# ethernetGateway.net
KiCad netlist of a schematic drawn in EAGLE
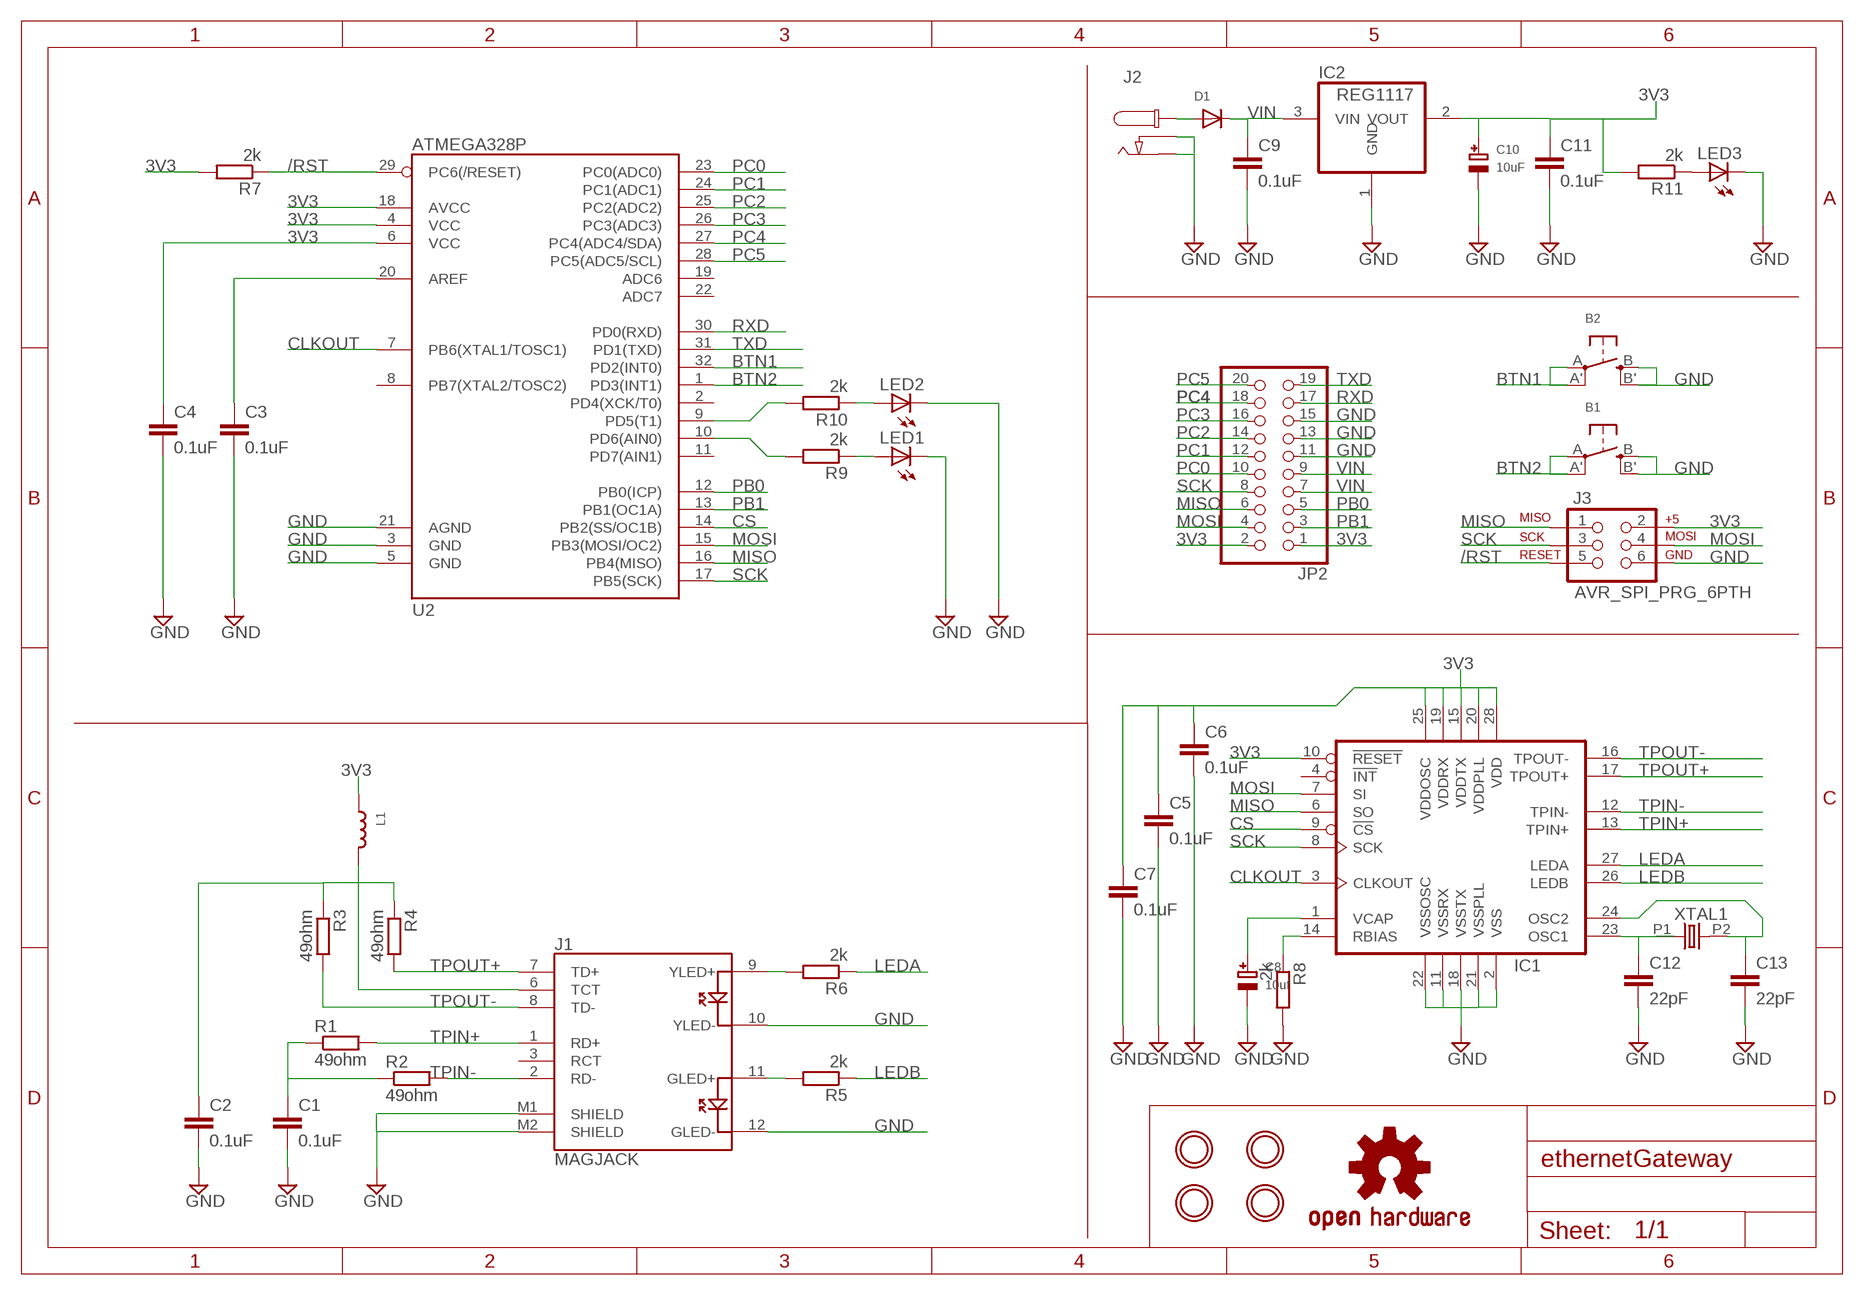
[diagram p0: schematic, sheet 1]

(export (version "E")
  (design (tool "Eeschema 10.0.6"))
  (components
    (comp (ref "B1")
      (value "SWITCH_TACT_SMT4.6X2.8")
      (footprint "eagle-import:BTN_KMR2_4.6X2.8")
      (libsource (lib "eagle-import") (part "SWITCH_TACT_SMT4.6X2.8"))
    )
    (comp (ref "B2")
      (value "SWITCH_TACT_SMT4.6X2.8")
      (footprint "eagle-import:BTN_KMR2_4.6X2.8")
      (libsource (lib "eagle-import") (part "SWITCH_TACT_SMT4.6X2.8"))
    )
    (comp (ref "C1")
      (value "0.1uF")
      (footprint "eagle-import:C0805")
      (libsource (lib "eagle-import") (part "C-EUC0805"))
    )
    (comp (ref "C2")
      (value "0.1uF")
      (footprint "eagle-import:C0805")
      (libsource (lib "eagle-import") (part "C-EUC0805"))
    )
    (comp (ref "C3")
      (value "0.1uF")
      (footprint "eagle-import:C0805")
      (libsource (lib "eagle-import") (part "C-EUC0805"))
    )
    (comp (ref "C4")
      (value "0.1uF")
      (footprint "eagle-import:C0805")
      (libsource (lib "eagle-import") (part "C-EUC0805"))
    )
    (comp (ref "C5")
      (value "0.1uF")
      (footprint "eagle-import:C0805")
      (libsource (lib "eagle-import") (part "C-EUC0805"))
    )
    (comp (ref "C6")
      (value "0.1uF")
      (footprint "eagle-import:C0805")
      (libsource (lib "eagle-import") (part "C-EUC0805"))
    )
    (comp (ref "C7")
      (value "0.1uF")
      (footprint "eagle-import:C0805")
      (libsource (lib "eagle-import") (part "C-EUC0805"))
    )
    (comp (ref "C8")
      (value "10uf")
      (footprint "eagle-import:EIA3528-21_B-W")
      (libsource (lib "eagle-import") (part "CAP_TANTALUMB/3528_WAVE"))
    )
    (comp (ref "C9")
      (value "0.1uF")
      (footprint "eagle-import:C0805")
      (libsource (lib "eagle-import") (part "C-EUC0805"))
    )
    (comp (ref "C10")
      (value "10uF")
      (footprint "eagle-import:EIA3528-21_B-W")
      (libsource (lib "eagle-import") (part "CAP_TANTALUMB/3528_WAVE"))
    )
    (comp (ref "C11")
      (value "0.1uF")
      (footprint "eagle-import:C0805")
      (libsource (lib "eagle-import") (part "C-EUC0805"))
    )
    (comp (ref "C12")
      (value "22pF")
      (footprint "eagle-import:C0805")
      (libsource (lib "eagle-import") (part "C-EUC0805"))
    )
    (comp (ref "C13")
      (value "22pF")
      (footprint "eagle-import:C0805")
      (libsource (lib "eagle-import") (part "C-EUC0805"))
    )
    (comp (ref "D1")
      (value "DIODEDO-1N4148")
      (footprint "eagle-import:DO-1N4148")
      (libsource (lib "eagle-import") (part "DIODEDO-1N4148"))
    )
    (comp (ref "IC1")
      (value "IC_ENC28J60-SOIC-28")
      (footprint "eagle-import:SOIC-28W")
      (libsource (lib "eagle-import") (part "IC_ENC28J60-SOIC-28"))
    )
    (comp (ref "IC2")
      (value "REG1117")
      (footprint "eagle-import:SOT223")
      (libsource (lib "eagle-import") (part "REG1117"))
    )
    (comp (ref "J1")
      (value "MAGJACK")
      (footprint "eagle-import:MAGJACK")
      (libsource (lib "eagle-import") (part "MAGJACK"))
    )
    (comp (ref "J2")
      (value "CON_DC_M-DC_PTH")
      (footprint "eagle-import:DC_BARREL_JACK_PTH_2MM")
      (libsource (lib "eagle-import") (part "CON_DC_M-DC_PTH"))
    )
    (comp (ref "J3")
      (value "AVR_SPI_PRG_6PTH")
      (footprint "eagle-import:2X3")
      (libsource (lib "eagle-import") (part "AVR_SPI_PRG_6PTH"))
    )
    (comp (ref "JP2")
      (value "PINHD-2X10")
      (footprint "eagle-import:2X10")
      (libsource (lib "eagle-import") (part "PINHD-2X10"))
    )
    (comp (ref "L1")
      (value "INDUCTOR0805")
      (footprint "eagle-import:0805")
      (libsource (lib "eagle-import") (part "INDUCTOR0805"))
    )
    (comp (ref "LED1")
      (value "LED-0805")
      (footprint "eagle-import:LED-805")
      (libsource (lib "eagle-import") (part "LED-0805"))
    )
    (comp (ref "LED2")
      (value "LED-0805")
      (footprint "eagle-import:LED-805")
      (libsource (lib "eagle-import") (part "LED-0805"))
    )
    (comp (ref "LED3")
      (value "LED-0805")
      (footprint "eagle-import:LED-805")
      (libsource (lib "eagle-import") (part "LED-0805"))
    )
    (comp (ref "LOGO1")
      (value "OSHW-LOGOL")
      (footprint "eagle-import:OSHW-LOGO-L")
      (libsource (lib "eagle-import") (part "OSHW-LOGOL"))
    )
    (comp (ref "R1")
      (value "49ohm")
      (footprint "eagle-import:R0805")
      (libsource (lib "eagle-import") (part "R-EU_R0805"))
    )
    (comp (ref "R2")
      (value "49ohm")
      (footprint "eagle-import:R0805")
      (libsource (lib "eagle-import") (part "R-EU_R0805"))
    )
    (comp (ref "R3")
      (value "49ohm")
      (footprint "eagle-import:R0805")
      (libsource (lib "eagle-import") (part "R-EU_R0805"))
    )
    (comp (ref "R4")
      (value "49ohm")
      (footprint "eagle-import:R0805")
      (libsource (lib "eagle-import") (part "R-EU_R0805"))
    )
    (comp (ref "R5")
      (value "2k")
      (footprint "eagle-import:R0805")
      (libsource (lib "eagle-import") (part "R-EU_R0805"))
    )
    (comp (ref "R6")
      (value "2k")
      (footprint "eagle-import:R0805")
      (libsource (lib "eagle-import") (part "R-EU_R0805"))
    )
    (comp (ref "R7")
      (value "2k")
      (footprint "eagle-import:R0805")
      (libsource (lib "eagle-import") (part "R-EU_R0805"))
    )
    (comp (ref "R8")
      (value "2k")
      (footprint "eagle-import:R0805")
      (libsource (lib "eagle-import") (part "R-EU_R0805"))
    )
    (comp (ref "R9")
      (value "2k")
      (footprint "eagle-import:R0805")
      (libsource (lib "eagle-import") (part "R-EU_R0805"))
    )
    (comp (ref "R10")
      (value "2k")
      (footprint "eagle-import:R0805")
      (libsource (lib "eagle-import") (part "R-EU_R0805"))
    )
    (comp (ref "R11")
      (value "2k")
      (footprint "eagle-import:R0805")
      (libsource (lib "eagle-import") (part "R-EU_R0805"))
    )
    (comp (ref "U$1")
      (value "MOUNTINGHOLE2.0")
      (footprint "eagle-import:MOUNTINGHOLE_2.0_PLATED")
      (libsource (lib "eagle-import") (part "MOUNTINGHOLE2.0"))
    )
    (comp (ref "U$2")
      (value "MOUNTINGHOLE2.0")
      (footprint "eagle-import:MOUNTINGHOLE_2.0_PLATED")
      (libsource (lib "eagle-import") (part "MOUNTINGHOLE2.0"))
    )
    (comp (ref "U$3")
      (value "MOUNTINGHOLE2.0")
      (footprint "eagle-import:MOUNTINGHOLE_2.0_PLATED")
      (libsource (lib "eagle-import") (part "MOUNTINGHOLE2.0"))
    )
    (comp (ref "U$4")
      (value "MOUNTINGHOLE2.0")
      (footprint "eagle-import:MOUNTINGHOLE_2.0_PLATED")
      (libsource (lib "eagle-import") (part "MOUNTINGHOLE2.0"))
    )
    (comp (ref "U2")
      (value "ATMEGA328P")
      (footprint "eagle-import:TQFP32-08")
      (libsource (lib "eagle-import") (part "ATMEGA328_SMT"))
    )
    (comp (ref "XTAL1")
      (value "OSC-XTAL-HC-49U-PTH")
      (footprint "eagle-import:HC-49U-PTH")
      (libsource (lib "eagle-import") (part "OSC-XTAL-HC-49U-PTH"))
    )
  )
  (nets
    (net (code "1") (name "/3V3") (class "Default")
      (node (ref "C10") (pin "+") (pinfunction "+_+") (pintype "passive"))
      (node (ref "C11") (pin "1") (pinfunction "1_1") (pintype "passive"))
      (node (ref "C4") (pin "1") (pinfunction "1_1") (pintype "passive"))
      (node (ref "C5") (pin "1") (pinfunction "1_1") (pintype "passive"))
      (node (ref "C6") (pin "1") (pinfunction "1_1") (pintype "passive"))
      (node (ref "C7") (pin "1") (pinfunction "1_1") (pintype "passive"))
      (node (ref "IC1") (pin "10") (pinfunction "~{RESET}_10") (pintype "input"))
      (node (ref "IC1") (pin "15") (pinfunction "VDDTX_15") (pintype "power_in"))
      (node (ref "IC1") (pin "19") (pinfunction "VDDRX_19") (pintype "power_in"))
      (node (ref "IC1") (pin "20") (pinfunction "VDDPLL_20") (pintype "power_in"))
      (node (ref "IC1") (pin "25") (pinfunction "VDDOSC_25") (pintype "power_in"))
      (node (ref "IC1") (pin "28") (pinfunction "VDD_28") (pintype "power_in"))
      (node (ref "IC2") (pin "2") (pinfunction "VOUT_2") (pintype "output"))
      (node (ref "J3") (pin "2") (pinfunction "2_2") (pintype "passive"))
      (node (ref "JP2") (pin "1") (pinfunction "1_1") (pintype "passive"))
      (node (ref "JP2") (pin "2") (pinfunction "2_2") (pintype "passive"))
      (node (ref "L1") (pin "1") (pinfunction "1_1") (pintype "passive"))
      (node (ref "R11") (pin "2") (pinfunction "2_2") (pintype "passive"))
      (node (ref "R7") (pin "2") (pinfunction "2_2") (pintype "passive"))
      (node (ref "U2") (pin "18") (pinfunction "AVCC_18") (pintype "bidirectional"))
      (node (ref "U2") (pin "4") (pinfunction "VCC_4") (pintype "bidirectional"))
      (node (ref "U2") (pin "6") (pinfunction "VCC_6") (pintype "bidirectional"))
    )
    (net (code "2") (name "/BTN1") (class "Default")
      (node (ref "B2") (pin "A") (pinfunction "P_A") (pintype "passive"))
      (node (ref "B2") (pin "A'") (pinfunction "P1_A'") (pintype "passive"))
      (node (ref "U2") (pin "32") (pinfunction "PD2(INT0)_32") (pintype "bidirectional"))
    )
    (net (code "3") (name "/BTN2") (class "Default")
      (node (ref "B1") (pin "A") (pinfunction "P_A") (pintype "passive"))
      (node (ref "B1") (pin "A'") (pinfunction "P1_A'") (pintype "passive"))
      (node (ref "U2") (pin "1") (pinfunction "PD3(INT1)_1") (pintype "bidirectional"))
    )
    (net (code "4") (name "/CLKOUT") (class "Default")
      (node (ref "IC1") (pin "3") (pinfunction "CLKOUT_3") (pintype "output"))
      (node (ref "U2") (pin "7") (pinfunction "PB6(XTAL1/TOSC1)_7") (pintype "bidirectional"))
    )
    (net (code "5") (name "/CS") (class "Default")
      (node (ref "IC1") (pin "9") (pinfunction "~{CS}_9") (pintype "input"))
      (node (ref "U2") (pin "14") (pinfunction "PB2(SS/OC1B)_14") (pintype "bidirectional"))
    )
    (net (code "6") (name "/LEDA") (class "Default")
      (node (ref "IC1") (pin "27") (pinfunction "LEDA_27") (pintype "output"))
      (node (ref "R6") (pin "1") (pinfunction "1_1") (pintype "passive"))
    )
    (net (code "7") (name "/LEDB") (class "Default")
      (node (ref "IC1") (pin "26") (pinfunction "LEDB_26") (pintype "output"))
      (node (ref "R5") (pin "1") (pinfunction "1_1") (pintype "passive"))
    )
    (net (code "8") (name "/MISO") (class "Default")
      (node (ref "IC1") (pin "6") (pinfunction "SO_6") (pintype "output"))
      (node (ref "J3") (pin "1") (pinfunction "1_1") (pintype "passive"))
      (node (ref "JP2") (pin "6") (pinfunction "6_6") (pintype "passive"))
      (node (ref "U2") (pin "16") (pinfunction "PB4(MISO)_16") (pintype "bidirectional"))
    )
    (net (code "9") (name "/MOSI") (class "Default")
      (node (ref "IC1") (pin "7") (pinfunction "SI_7") (pintype "input"))
      (node (ref "J3") (pin "4") (pinfunction "4_4") (pintype "passive"))
      (node (ref "JP2") (pin "4") (pinfunction "4_4") (pintype "passive"))
      (node (ref "U2") (pin "15") (pinfunction "PB3(MOSI/OC2)_15") (pintype "bidirectional"))
    )
    (net (code "10") (name "/PB0") (class "Default")
      (node (ref "JP2") (pin "5") (pinfunction "5_5") (pintype "passive"))
      (node (ref "U2") (pin "12") (pinfunction "PB0(ICP)_12") (pintype "bidirectional"))
    )
    (net (code "11") (name "/PB1") (class "Default")
      (node (ref "JP2") (pin "3") (pinfunction "3_3") (pintype "passive"))
      (node (ref "U2") (pin "13") (pinfunction "PB1(OC1A)_13") (pintype "bidirectional"))
    )
    (net (code "12") (name "/PC0") (class "Default")
      (node (ref "JP2") (pin "10") (pinfunction "10_10") (pintype "passive"))
      (node (ref "U2") (pin "23") (pinfunction "PC0(ADC0)_23") (pintype "bidirectional"))
    )
    (net (code "13") (name "/PC1") (class "Default")
      (node (ref "JP2") (pin "12") (pinfunction "12_12") (pintype "passive"))
      (node (ref "U2") (pin "24") (pinfunction "PC1(ADC1)_24") (pintype "bidirectional"))
    )
    (net (code "14") (name "/PC2") (class "Default")
      (node (ref "JP2") (pin "14") (pinfunction "14_14") (pintype "passive"))
      (node (ref "U2") (pin "25") (pinfunction "PC2(ADC2)_25") (pintype "bidirectional"))
    )
    (net (code "15") (name "/PC3") (class "Default")
      (node (ref "JP2") (pin "16") (pinfunction "16_16") (pintype "passive"))
      (node (ref "U2") (pin "26") (pinfunction "PC3(ADC3)_26") (pintype "bidirectional"))
    )
    (net (code "16") (name "/PC4") (class "Default")
      (node (ref "JP2") (pin "18") (pinfunction "18_18") (pintype "passive"))
      (node (ref "U2") (pin "27") (pinfunction "PC4(ADC4/SDA)_27") (pintype "bidirectional"))
    )
    (net (code "17") (name "/PC5") (class "Default")
      (node (ref "JP2") (pin "20") (pinfunction "20_20") (pintype "passive"))
      (node (ref "U2") (pin "28") (pinfunction "PC5(ADC5/SCL)_28") (pintype "bidirectional"))
    )
    (net (code "18") (name "/RXD") (class "Default")
      (node (ref "JP2") (pin "17") (pinfunction "17_17") (pintype "passive"))
      (node (ref "U2") (pin "30") (pinfunction "PD0(RXD)_30") (pintype "bidirectional"))
    )
    (net (code "19") (name "/SCK") (class "Default")
      (node (ref "IC1") (pin "8") (pinfunction "SCK_8") (pintype "input"))
      (node (ref "J3") (pin "3") (pinfunction "3_3") (pintype "passive"))
      (node (ref "JP2") (pin "8") (pinfunction "8_8") (pintype "passive"))
      (node (ref "U2") (pin "17") (pinfunction "PB5(SCK)_17") (pintype "bidirectional"))
    )
    (net (code "20") (name "/TPIN+") (class "Default")
      (node (ref "IC1") (pin "13") (pinfunction "TPIN+_13") (pintype "input"))
      (node (ref "J1") (pin "1") (pinfunction "RD+_1") (pintype "bidirectional"))
      (node (ref "R1") (pin "2") (pinfunction "2_2") (pintype "passive"))
    )
    (net (code "21") (name "/TPIN-") (class "Default")
      (node (ref "IC1") (pin "12") (pinfunction "TPIN-_12") (pintype "input"))
      (node (ref "J1") (pin "2") (pinfunction "RD-_2") (pintype "bidirectional"))
      (node (ref "R2") (pin "2") (pinfunction "2_2") (pintype "passive"))
    )
    (net (code "22") (name "/TPOUT+") (class "Default")
      (node (ref "IC1") (pin "17") (pinfunction "TPOUT+_17") (pintype "output"))
      (node (ref "J1") (pin "7") (pinfunction "TD+_7") (pintype "bidirectional"))
      (node (ref "R4") (pin "2") (pinfunction "2_2") (pintype "passive"))
    )
    (net (code "23") (name "/TPOUT-") (class "Default")
      (node (ref "IC1") (pin "16") (pinfunction "TPOUT-_16") (pintype "output"))
      (node (ref "J1") (pin "8") (pinfunction "TD-_8") (pintype "bidirectional"))
      (node (ref "R3") (pin "2") (pinfunction "2_2") (pintype "passive"))
    )
    (net (code "24") (name "/TXD") (class "Default")
      (node (ref "JP2") (pin "19") (pinfunction "19_19") (pintype "passive"))
      (node (ref "U2") (pin "31") (pinfunction "PD1(TXD)_31") (pintype "bidirectional"))
    )
    (net (code "25") (name "/VIN") (class "Default")
      (node (ref "C9") (pin "1") (pinfunction "1_1") (pintype "passive"))
      (node (ref "D1") (pin "C") (pinfunction "C_C") (pintype "passive"))
      (node (ref "IC2") (pin "3") (pinfunction "VIN_3") (pintype "input"))
      (node (ref "JP2") (pin "7") (pinfunction "7_7") (pintype "passive"))
      (node (ref "JP2") (pin "9") (pinfunction "9_9") (pintype "passive"))
    )
    (net (code "26") (name "/{slash}RST") (class "Default")
      (node (ref "J3") (pin "5") (pinfunction "5_5") (pintype "passive"))
      (node (ref "R7") (pin "1") (pinfunction "1_1") (pintype "passive"))
      (node (ref "U2") (pin "29") (pinfunction "PC6(/RESET)_29") (pintype "bidirectional"))
    )
    (net (code "27") (name "GND") (class "Default")
      (node (ref "B1") (pin "B") (pinfunction "S_B") (pintype "passive"))
      (node (ref "B1") (pin "B'") (pinfunction "S1_B'") (pintype "passive"))
      (node (ref "B2") (pin "B") (pinfunction "S_B") (pintype "passive"))
      (node (ref "B2") (pin "B'") (pinfunction "S1_B'") (pintype "passive"))
      (node (ref "C1") (pin "2") (pinfunction "2_2") (pintype "passive"))
      (node (ref "C10") (pin "-") (pinfunction "-_-") (pintype "passive"))
      (node (ref "C11") (pin "2") (pinfunction "2_2") (pintype "passive"))
      (node (ref "C12") (pin "2") (pinfunction "2_2") (pintype "passive"))
      (node (ref "C13") (pin "2") (pinfunction "2_2") (pintype "passive"))
      (node (ref "C2") (pin "2") (pinfunction "2_2") (pintype "passive"))
      (node (ref "C3") (pin "2") (pinfunction "2_2") (pintype "passive"))
      (node (ref "C4") (pin "2") (pinfunction "2_2") (pintype "passive"))
      (node (ref "C5") (pin "2") (pinfunction "2_2") (pintype "passive"))
      (node (ref "C6") (pin "2") (pinfunction "2_2") (pintype "passive"))
      (node (ref "C7") (pin "2") (pinfunction "2_2") (pintype "passive"))
      (node (ref "C8") (pin "-") (pinfunction "-_-") (pintype "passive"))
      (node (ref "C9") (pin "2") (pinfunction "2_2") (pintype "passive"))
      (node (ref "IC1") (pin "11") (pinfunction "VSSRX_11") (pintype "power_in"))
      (node (ref "IC1") (pin "18") (pinfunction "VSSTX_18") (pintype "power_in"))
      (node (ref "IC1") (pin "2") (pinfunction "VSS_2") (pintype "power_in"))
      (node (ref "IC1") (pin "21") (pinfunction "VSSPLL_21") (pintype "power_in"))
      (node (ref "IC1") (pin "22") (pinfunction "VSSOSC_22") (pintype "power_in"))
      (node (ref "IC2") (pin "1") (pinfunction "GND_1") (pintype "power_in"))
      (node (ref "J1") (pin "10") (pinfunction "YLED-_10") (pintype "bidirectional"))
      (node (ref "J1") (pin "12") (pinfunction "GLED-_12") (pintype "bidirectional"))
      (node (ref "J1") (pin "M1") (pinfunction "SHIELD_M1") (pintype "bidirectional"))
      (node (ref "J1") (pin "M2") (pinfunction "SHIELD_M2") (pintype "bidirectional"))
      (node (ref "J2") (pin "P2") (pinfunction "P3_P2") (pintype "passive"))
      (node (ref "J2") (pin "P3") (pinfunction "P2_P3") (pintype "passive"))
      (node (ref "J3") (pin "6") (pinfunction "6_6") (pintype "passive"))
      (node (ref "JP2") (pin "11") (pinfunction "11_11") (pintype "passive"))
      (node (ref "JP2") (pin "13") (pinfunction "13_13") (pintype "passive"))
      (node (ref "JP2") (pin "15") (pinfunction "15_15") (pintype "passive"))
      (node (ref "LED1") (pin "C") (pinfunction "C_C") (pintype "passive"))
      (node (ref "LED2") (pin "C") (pinfunction "C_C") (pintype "passive"))
      (node (ref "LED3") (pin "C") (pinfunction "C_C") (pintype "passive"))
      (node (ref "R8") (pin "2") (pinfunction "2_2") (pintype "passive"))
      (node (ref "U2") (pin "21") (pinfunction "AGND_21") (pintype "bidirectional"))
      (node (ref "U2") (pin "3") (pinfunction "GND_3") (pintype "bidirectional"))
      (node (ref "U2") (pin "5") (pinfunction "GND_5") (pintype "bidirectional"))
    )
    (net (code "28") (name "Net-(C1-Pad1)") (class "Default")
      (node (ref "C1") (pin "1") (pinfunction "1_1") (pintype "passive"))
      (node (ref "R1") (pin "1") (pinfunction "1_1") (pintype "passive"))
      (node (ref "R2") (pin "1") (pinfunction "1_1") (pintype "passive"))
    )
    (net (code "29") (name "Net-(D1-PadA)") (class "Default")
      (node (ref "D1") (pin "A") (pinfunction "A_A") (pintype "passive"))
      (node (ref "J2") (pin "P1") (pinfunction "P1_P1") (pintype "passive"))
    )
    (net (code "30") (name "Net-(IC1-OSC1)") (class "Default")
      (node (ref "C12") (pin "1") (pinfunction "1_1") (pintype "passive"))
      (node (ref "IC1") (pin "23") (pinfunction "OSC1_23") (pintype "input"))
      (node (ref "XTAL1") (pin "P1") (pinfunction "1_P1") (pintype "passive"))
    )
    (net (code "31") (name "Net-(IC1-OSC2)") (class "Default")
      (node (ref "C13") (pin "1") (pinfunction "1_1") (pintype "passive"))
      (node (ref "IC1") (pin "24") (pinfunction "OSC2_24") (pintype "output"))
      (node (ref "XTAL1") (pin "P2") (pinfunction "2_P2") (pintype "passive"))
    )
    (net (code "32") (name "Net-(IC1-RBIAS)") (class "Default")
      (node (ref "IC1") (pin "14") (pinfunction "RBIAS_14") (pintype "input"))
      (node (ref "R8") (pin "1") (pinfunction "1_1") (pintype "passive"))
    )
    (net (code "33") (name "Net-(IC1-VCAP)") (class "Default")
      (node (ref "C8") (pin "+") (pinfunction "+_+") (pintype "passive"))
      (node (ref "IC1") (pin "1") (pinfunction "VCAP_1") (pintype "input"))
    )
    (net (code "34") (name "Net-(J1-GLED+)") (class "Default")
      (node (ref "J1") (pin "11") (pinfunction "GLED+_11") (pintype "bidirectional"))
      (node (ref "R5") (pin "2") (pinfunction "2_2") (pintype "passive"))
    )
    (net (code "35") (name "Net-(J1-TCT)") (class "Default")
      (node (ref "C2") (pin "1") (pinfunction "1_1") (pintype "passive"))
      (node (ref "J1") (pin "6") (pinfunction "TCT_6") (pintype "bidirectional"))
      (node (ref "L1") (pin "2") (pinfunction "2_2") (pintype "passive"))
      (node (ref "R3") (pin "1") (pinfunction "1_1") (pintype "passive"))
      (node (ref "R4") (pin "1") (pinfunction "1_1") (pintype "passive"))
    )
    (net (code "36") (name "Net-(J1-YLED+)") (class "Default")
      (node (ref "J1") (pin "9") (pinfunction "YLED+_9") (pintype "bidirectional"))
      (node (ref "R6") (pin "2") (pinfunction "2_2") (pintype "passive"))
    )
    (net (code "37") (name "Net-(LED1-PadA)") (class "Default")
      (node (ref "LED1") (pin "A") (pinfunction "A_A") (pintype "passive"))
      (node (ref "R9") (pin "1") (pinfunction "1_1") (pintype "passive"))
    )
    (net (code "38") (name "Net-(LED2-PadA)") (class "Default")
      (node (ref "LED2") (pin "A") (pinfunction "A_A") (pintype "passive"))
      (node (ref "R10") (pin "1") (pinfunction "1_1") (pintype "passive"))
    )
    (net (code "39") (name "Net-(LED3-PadA)") (class "Default")
      (node (ref "LED3") (pin "A") (pinfunction "A_A") (pintype "passive"))
      (node (ref "R11") (pin "1") (pinfunction "1_1") (pintype "passive"))
    )
    (net (code "40") (name "Net-(U2-AREF)") (class "Default")
      (node (ref "C3") (pin "1") (pinfunction "1_1") (pintype "passive"))
      (node (ref "U2") (pin "20") (pinfunction "AREF_20") (pintype "bidirectional"))
    )
    (net (code "41") (name "Net-(U2-PD5(T1))") (class "Default")
      (node (ref "R10") (pin "2") (pinfunction "2_2") (pintype "passive"))
      (node (ref "U2") (pin "9") (pinfunction "PD5(T1)_9") (pintype "bidirectional"))
    )
    (net (code "42") (name "Net-(U2-PD6(AIN0))") (class "Default")
      (node (ref "R9") (pin "2") (pinfunction "2_2") (pintype "passive"))
      (node (ref "U2") (pin "10") (pinfunction "PD6(AIN0)_10") (pintype "bidirectional"))
    )
    (net (code "43") (name "unconnected-(IC1-~{INT}-Pad4)") (class "Default")
      (node (ref "IC1") (pin "4") (pinfunction "~{INT}_4") (pintype "output"))
    )
    (net (code "44") (name "unconnected-(J1-RCT-Pad3)") (class "Default")
      (node (ref "J1") (pin "3") (pinfunction "RCT_3") (pintype "bidirectional"))
    )
    (net (code "45") (name "unconnected-(U2-ADC6-Pad19)") (class "Default")
      (node (ref "U2") (pin "19") (pinfunction "ADC6_19") (pintype "bidirectional"))
    )
    (net (code "46") (name "unconnected-(U2-ADC7-Pad22)") (class "Default")
      (node (ref "U2") (pin "22") (pinfunction "ADC7_22") (pintype "bidirectional"))
    )
    (net (code "47") (name "unconnected-(U2-PB7(XTAL2{slash}TOSC2)-Pad8)") (class "Default")
      (node (ref "U2") (pin "8") (pinfunction "PB7(XTAL2/TOSC2)_8") (pintype "bidirectional"))
    )
    (net (code "48") (name "unconnected-(U2-PD4(XCK{slash}T0)-Pad2)") (class "Default")
      (node (ref "U2") (pin "2") (pinfunction "PD4(XCK/T0)_2") (pintype "bidirectional"))
    )
    (net (code "49") (name "unconnected-(U2-PD7(AIN1)-Pad11)") (class "Default")
      (node (ref "U2") (pin "11") (pinfunction "PD7(AIN1)_11") (pintype "bidirectional"))
    )
  )
)
